# CAN_schematic.net
KiCad netlist of a schematic drawn in Altium Designer
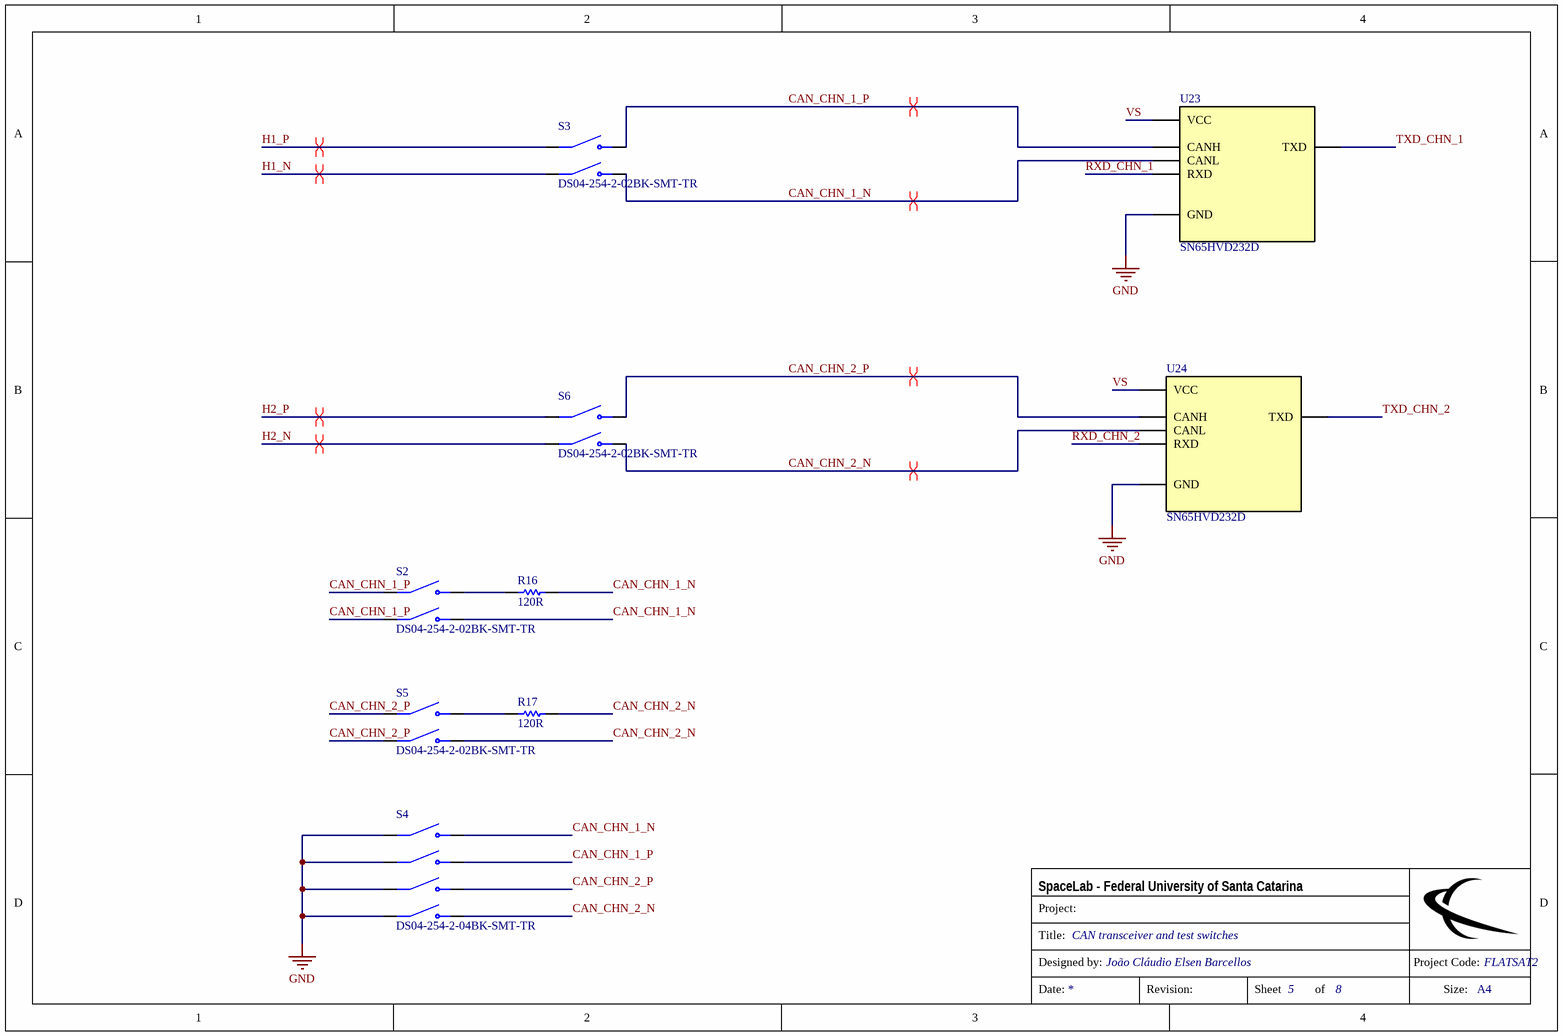
[diagram p0: CAN_schematic.SchDoc]

(export (version "E")
  (design (tool "Eeschema 10.0.6"))
  (components
    (comp (ref "R16")
      (value "120R")
      (footprint "0805")
      (description "RES 120R OHM 1/8W 1% 0805")
      (fields (field (name "MANUFACTURER PART NUMBER") "CRGCQ0805F120R"))
      (libsource (lib "flatsat_platform_2") (part "R120R_1%_1/4W_0805"))
    )
    (comp (ref "R17")
      (value "120R")
      (footprint "0805")
      (description "RES 120R OHM 1/8W 1% 0805")
      (fields (field (name "MANUFACTURER PART NUMBER") "CRGCQ0805F120R"))
      (libsource (lib "flatsat_platform_2") (part "R120R_1%_1/4W_0805"))
    )
    (comp (ref "S2")
      (value "DS04-254-2-02BK-SMT-TR")
      (footprint "SW_DS04-254-2-02BK-SMT-TR")
      (description "1 ~ 12 positions, Surface Mount, 2.54 mm Pitch, Slide Actuator, DIP Switch")
      (fields (field (name "MF") "CUI Devices"))
      (libsource (lib "flatsat_platform_2") (part "DS04-254-2-02BK-SMT-TR"))
    )
    (comp (ref "S3")
      (value "DS04-254-2-02BK-SMT-TR")
      (footprint "SW_DS04-254-2-02BK-SMT-TR")
      (description "1 ~ 12 positions, Surface Mount, 2.54 mm Pitch, Slide Actuator, DIP Switch")
      (fields (field (name "MF") "CUI Devices"))
      (libsource (lib "flatsat_platform_2") (part "DS04-254-2-02BK-SMT-TR"))
    )
    (comp (ref "S4")
      (value "DS04-254-2-04BK-SMT-TR")
      (footprint "SW_DS04-254-2-04BK-SMT-TR")
      (description "1 ~ 12 positions, Surface Mount, 2.54 mm Pitch, Slide Actuator, DIP Switch")
      (fields (field (name "MF") "CUI Devices"))
      (libsource (lib "flatsat_platform_2") (part "DS04-254-2-04BK-SMT-TR"))
    )
    (comp (ref "S5")
      (value "DS04-254-2-02BK-SMT-TR")
      (footprint "SW_DS04-254-2-02BK-SMT-TR")
      (description "1 ~ 12 positions, Surface Mount, 2.54 mm Pitch, Slide Actuator, DIP Switch")
      (fields (field (name "MF") "CUI Devices"))
      (libsource (lib "flatsat_platform_2") (part "DS04-254-2-02BK-SMT-TR"))
    )
    (comp (ref "S6")
      (value "DS04-254-2-02BK-SMT-TR")
      (footprint "SW_DS04-254-2-02BK-SMT-TR")
      (description "1 ~ 12 positions, Surface Mount, 2.54 mm Pitch, Slide Actuator, DIP Switch")
      (fields (field (name "MF") "CUI Devices"))
      (libsource (lib "flatsat_platform_2") (part "DS04-254-2-02BK-SMT-TR"))
    )
    (comp (ref "U23")
      (value "SN65HVD232D")
      (footprint "SOIC127P599X175-8N")
      (description "3.3 V CAN Transceiver")
      (fields (field (name "MF") "Texas Instruments"))
      (libsource (lib "flatsat_platform_2") (part "SN65HVD232D"))
    )
    (comp (ref "U24")
      (value "SN65HVD232D")
      (footprint "SOIC127P599X175-8N")
      (description "3.3 V CAN Transceiver")
      (fields (field (name "MF") "Texas Instruments"))
      (libsource (lib "flatsat_platform_2") (part "SN65HVD232D"))
    )
  )
  (nets
    (net (code "1") (name "/CAN_CHN_1_N") (class "Default")
      (node (ref "R16") (pin "1") (pinfunction "1_1") (pintype "passive"))
      (node (ref "S2") (pin "2B") (pinfunction "NO2_2B") (pintype "passive"))
      (node (ref "S3") (pin "2B") (pinfunction "NO2_2B") (pintype "passive"))
      (node (ref "S4") (pin "1B") (pinfunction "NO1_1B") (pintype "passive"))
      (node (ref "U23") (pin "6") (pinfunction "CANL_6") (pintype "power_in"))
    )
    (net (code "2") (name "/CAN_CHN_1_P") (class "Default")
      (node (ref "S2") (pin "1A") (pinfunction "COM1_1A") (pintype "passive"))
      (node (ref "S2") (pin "2A") (pinfunction "COM2_2A") (pintype "passive"))
      (node (ref "S3") (pin "1B") (pinfunction "NO1_1B") (pintype "passive"))
      (node (ref "S4") (pin "2B") (pinfunction "NO2_2B") (pintype "passive"))
      (node (ref "U23") (pin "7") (pinfunction "CANH_7") (pintype "power_in"))
    )
    (net (code "3") (name "/CAN_CHN_2_N") (class "Default")
      (node (ref "R17") (pin "1") (pinfunction "1_1") (pintype "passive"))
      (node (ref "S4") (pin "4B") (pinfunction "NO4_4B") (pintype "passive"))
      (node (ref "S5") (pin "2B") (pinfunction "NO2_2B") (pintype "passive"))
      (node (ref "S6") (pin "2B") (pinfunction "NO2_2B") (pintype "passive"))
      (node (ref "U24") (pin "6") (pinfunction "CANL_6") (pintype "power_in"))
    )
    (net (code "4") (name "/CAN_CHN_2_P") (class "Default")
      (node (ref "S4") (pin "3B") (pinfunction "NO3_3B") (pintype "passive"))
      (node (ref "S5") (pin "1A") (pinfunction "COM1_1A") (pintype "passive"))
      (node (ref "S5") (pin "2A") (pinfunction "COM2_2A") (pintype "passive"))
      (node (ref "S6") (pin "1B") (pinfunction "NO1_1B") (pintype "passive"))
      (node (ref "U24") (pin "7") (pinfunction "CANH_7") (pintype "power_in"))
    )
    (net (code "5") (name "/H1_N") (class "Default")
      (node (ref "S3") (pin "2A") (pinfunction "COM2_2A") (pintype "passive"))
    )
    (net (code "6") (name "/H1_P") (class "Default")
      (node (ref "S3") (pin "1A") (pinfunction "COM1_1A") (pintype "passive"))
    )
    (net (code "7") (name "/H2_N") (class "Default")
      (node (ref "S6") (pin "2A") (pinfunction "COM2_2A") (pintype "passive"))
    )
    (net (code "8") (name "/H2_P") (class "Default")
      (node (ref "S6") (pin "1A") (pinfunction "COM1_1A") (pintype "passive"))
    )
    (net (code "9") (name "/RXD_CHN_1") (class "Default")
      (node (ref "U23") (pin "4") (pinfunction "RXD_4") (pintype "power_in"))
    )
    (net (code "10") (name "/RXD_CHN_2") (class "Default")
      (node (ref "U24") (pin "4") (pinfunction "RXD_4") (pintype "power_in"))
    )
    (net (code "11") (name "/TXD_CHN_1") (class "Default")
      (node (ref "U23") (pin "1") (pinfunction "TXD_1") (pintype "power_in"))
    )
    (net (code "12") (name "/TXD_CHN_2") (class "Default")
      (node (ref "U24") (pin "1") (pinfunction "TXD_1") (pintype "power_in"))
    )
    (net (code "13") (name "/VS") (class "Default")
      (node (ref "U23") (pin "3") (pinfunction "VCC_3") (pintype "power_in"))
      (node (ref "U24") (pin "3") (pinfunction "VCC_3") (pintype "power_in"))
    )
    (net (code "14") (name "GND") (class "Default")
      (node (ref "S4") (pin "1A") (pinfunction "COM1_1A") (pintype "passive"))
      (node (ref "S4") (pin "2A") (pinfunction "COM2_2A") (pintype "passive"))
      (node (ref "S4") (pin "3A") (pinfunction "COM3_3A") (pintype "passive"))
      (node (ref "S4") (pin "4A") (pinfunction "COM4_4A") (pintype "passive"))
      (node (ref "U23") (pin "2") (pinfunction "GND_2") (pintype "power_in"))
      (node (ref "U24") (pin "2") (pinfunction "GND_2") (pintype "power_in"))
    )
    (net (code "15") (name "Net-(S2-NO1)") (class "Default")
      (node (ref "R16") (pin "2") (pinfunction "2_2") (pintype "passive"))
      (node (ref "S2") (pin "1B") (pinfunction "NO1_1B") (pintype "passive"))
    )
    (net (code "16") (name "Net-(S5-NO1)") (class "Default")
      (node (ref "R17") (pin "2") (pinfunction "2_2") (pintype "passive"))
      (node (ref "S5") (pin "1B") (pinfunction "NO1_1B") (pintype "passive"))
    )
  )
)
